# 380_PCB_Design.net
KiCad netlist of a schematic drawn in Altium Designer
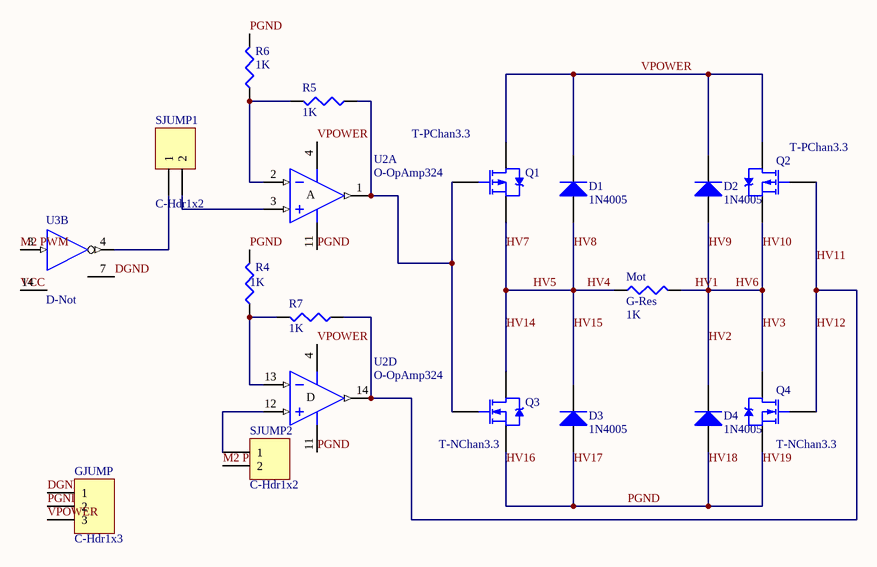
[diagram p0: 380 PCB Design.SchDoc]

(export (version "E")
  (design (tool "Eeschema 10.0.6"))
  (components
    (comp (ref "D1")
      (value "1N4005")
      (footprint "DO-41_XLGE1.2")
      (description "diode")
      (fields (field (name "PUBLISHER") "Altium Limited"))
      (libsource (lib "PartsDatabaseV12") (part "T-Diode-1N4005"))
    )
    (comp (ref "D2")
      (value "1N4005")
      (footprint "DO-41_XLGE1.2")
      (description "diode")
      (fields (field (name "PUBLISHER") "Altium Limited"))
      (libsource (lib "PartsDatabaseV12") (part "T-Diode-1N4005"))
    )
    (comp (ref "D3")
      (value "1N4005")
      (footprint "DO-41_XLGE1.2")
      (description "diode")
      (fields (field (name "PUBLISHER") "Altium Limited"))
      (libsource (lib "PartsDatabaseV12") (part "T-Diode-1N4005"))
    )
    (comp (ref "D4")
      (value "1N4005")
      (footprint "DO-41_XLGE1.2")
      (description "diode")
      (fields (field (name "PUBLISHER") "Altium Limited"))
      (libsource (lib "PartsDatabaseV12") (part "T-Diode-1N4005"))
    )
    (comp (ref "GJUMP")
      (value "C-Hdr1x3")
      (footprint "HDR1X3_LGE1.0")
      (description "Header, 4-Pin")
      (fields (field (name "PUBLISHER") "Altium Limited"))
      (libsource (lib "PartsDatabaseV13p1") (part "C-Hdr1x3"))
    )
    (comp (ref "Mot")
      (value "G-Res")
      (footprint "Res10mm_LGE1.0")
      (description "resistor (specify value)")
      (fields (field (name "ALTIUM_VALUE") "1K") (field (name "PUBLISHER") "Altium Limited"))
      (libsource (lib "PartsDatabaseV13p1") (part "G-Res"))
    )
    (comp (ref "Q1")
      (value "T-PChan3.3")
      (footprint "TO-220AB")
      (description "P-Channel Power MOSFET")
      (libsource (lib "PartsDatabaseV13p1") (part "T-PChan3.3"))
    )
    (comp (ref "Q2")
      (value "T-PChan3.3")
      (footprint "TO-220AB")
      (description "P-Channel Power MOSFET")
      (libsource (lib "PartsDatabaseV13p1") (part "T-PChan3.3"))
    )
    (comp (ref "Q3")
      (value "T-NChan3.3")
      (footprint "TO-220AB")
      (description "N-Channel Power MOSFET")
      (libsource (lib "PartsDatabaseV13p1") (part "T-NChan3.3"))
    )
    (comp (ref "Q4")
      (value "T-NChan3.3")
      (footprint "TO-220AB")
      (description "N-Channel Power MOSFET")
      (libsource (lib "PartsDatabaseV13p1") (part "T-NChan3.3"))
    )
    (comp (ref "R4")
      (value "1K")
      (footprint "Res10mm_LGE1.0")
      (description "resistor (specify value)")
      (fields (field (name "PUBLISHER") "Altium Limited"))
      (libsource (lib "PartsDatabaseV13p1") (part "G-Res"))
    )
    (comp (ref "R5")
      (value "1K")
      (footprint "Res10mm_LGE1.0")
      (description "resistor (specify value)")
      (fields (field (name "PUBLISHER") "Altium Limited"))
      (libsource (lib "PartsDatabaseV13p1") (part "G-Res"))
    )
    (comp (ref "R6")
      (value "1K")
      (footprint "Res10mm_LGE1.0")
      (description "resistor (specify value)")
      (fields (field (name "PUBLISHER") "Altium Limited"))
      (libsource (lib "PartsDatabaseV13p1") (part "G-Res"))
    )
    (comp (ref "R7")
      (value "1K")
      (footprint "Res10mm_LGE1.0")
      (description "resistor (specify value)")
      (fields (field (name "PUBLISHER") "Altium Limited"))
      (libsource (lib "PartsDatabaseV13p1") (part "G-Res"))
    )
    (comp (ref "SJUMP1")
      (value "C-Hdr1x2")
      (footprint "HDR1X2_LGE1.0")
      (description "Header, 2-Pin")
      (fields (field (name "PUBLISHER") "Altium Limited"))
      (libsource (lib "PartsDatabaseV13p1") (part "C-Hdr1x2"))
    )
    (comp (ref "SJUMP2")
      (value "C-Hdr1x2")
      (footprint "HDR1X2_LGE1.0")
      (description "Header, 2-Pin")
      (fields (field (name "PUBLISHER") "Altium Limited"))
      (libsource (lib "") (part "C-Hdr1x2_1"))
    )
    (comp (ref "U2")
      (value "O-OpAmp324")
      (footprint "DIP14_LGE1.0")
      (description "quad op-amp")
      (fields (field (name "PUBLISHER") "Altium Limited"))
      (libsource (lib "PartsDatabaseV13p1") (part "O-OpAmp324"))
    )
    (comp (ref "U3")
      (value "D-Not")
      (footprint "DIP14_LGE1.0")
      (description "hex NOT gate (inverter)")
      (fields (field (name "PUBLISHER") "Altium Limited"))
      (libsource (lib "PartsDatabaseV13p1") (part "D-Not"))
    )
  )
  (nets
    (net (code "1") (name "/DGND") (class "Default")
      (node (ref "GJUMP") (pin "1") (pinfunction "1_1") (pintype "passive"))
      (node (ref "U3") (pin "7") (pinfunction "GND_7") (pintype "power_in"))
    )
    (net (code "2") (name "/HV1") (class "Default")
      (node (ref "D2") (pin "1") (pinfunction "A_1") (pintype "passive"))
      (node (ref "D4") (pin "2") (pinfunction "K_2") (pintype "passive"))
      (node (ref "Mot") (pin "2") (pinfunction "2_2") (pintype "passive"))
      (node (ref "Q2") (pin "3") (pinfunction "S_3") (pintype "passive"))
      (node (ref "Q4") (pin "2") (pinfunction "D_2") (pintype "passive"))
    )
    (net (code "3") (name "/HV11") (class "Default")
      (node (ref "Q2") (pin "1") (pinfunction "G_1") (pintype "passive"))
      (node (ref "Q4") (pin "1") (pinfunction "G_1") (pintype "passive"))
      (node (ref "R7") (pin "1") (pinfunction "1_1") (pintype "passive"))
      (node (ref "U2") (pin "14") (pinfunction "OUT_14") (pintype "output"))
    )
    (net (code "4") (name "/HV14") (class "Default")
      (node (ref "D1") (pin "1") (pinfunction "A_1") (pintype "passive"))
      (node (ref "D3") (pin "2") (pinfunction "K_2") (pintype "passive"))
      (node (ref "Mot") (pin "1") (pinfunction "1_1") (pintype "passive"))
      (node (ref "Q1") (pin "3") (pinfunction "S_3") (pintype "passive"))
      (node (ref "Q3") (pin "2") (pinfunction "D_2") (pintype "passive"))
    )
    (net (code "5") (name "/HV16") (class "Default")
      (node (ref "D3") (pin "1") (pinfunction "A_1") (pintype "passive"))
      (node (ref "D4") (pin "1") (pinfunction "A_1") (pintype "passive"))
      (node (ref "GJUMP") (pin "2") (pinfunction "2_2") (pintype "passive"))
      (node (ref "Q3") (pin "3") (pinfunction "S_3") (pintype "passive"))
      (node (ref "Q4") (pin "3") (pinfunction "S_3") (pintype "passive"))
      (node (ref "R4") (pin "2") (pinfunction "2_2") (pintype "passive"))
      (node (ref "R6") (pin "2") (pinfunction "2_2") (pintype "passive"))
      (node (ref "U2") (pin "11") (pinfunction "V-_11") (pintype "power_in"))
    )
    (net (code "6") (name "/M2 PWM") (class "Default")
      (node (ref "SJUMP2") (pin "2") (pinfunction "2_2") (pintype "passive"))
      (node (ref "U3") (pin "3") (pinfunction "A_3") (pintype "input"))
    )
    (net (code "7") (name "/VCC") (class "Default")
      (node (ref "U3") (pin "14") (pinfunction "VCC_14") (pintype "power_in"))
    )
    (net (code "8") (name "/VPOWER") (class "Default")
      (node (ref "D1") (pin "2") (pinfunction "K_2") (pintype "passive"))
      (node (ref "D2") (pin "2") (pinfunction "K_2") (pintype "passive"))
      (node (ref "GJUMP") (pin "3") (pinfunction "3_3") (pintype "passive"))
      (node (ref "Q1") (pin "2") (pinfunction "D_2") (pintype "passive"))
      (node (ref "Q2") (pin "2") (pinfunction "D_2") (pintype "passive"))
      (node (ref "U2") (pin "4") (pinfunction "V+_4") (pintype "power_in"))
    )
    (net (code "9") (name "Net-(Q1-G)") (class "Default")
      (node (ref "Q1") (pin "1") (pinfunction "G_1") (pintype "passive"))
      (node (ref "Q3") (pin "1") (pinfunction "G_1") (pintype "passive"))
      (node (ref "R5") (pin "1") (pinfunction "1_1") (pintype "passive"))
      (node (ref "U2") (pin "1") (pinfunction "OUT_1") (pintype "output"))
    )
    (net (code "10") (name "Net-(U2A-IN+)") (class "Default")
      (node (ref "SJUMP1") (pin "2") (pinfunction "2_2") (pintype "passive"))
      (node (ref "U2") (pin "3") (pinfunction "IN+_3") (pintype "input"))
    )
    (net (code "11") (name "Net-(U2A-IN-)") (class "Default")
      (node (ref "R5") (pin "2") (pinfunction "2_2") (pintype "passive"))
      (node (ref "R6") (pin "1") (pinfunction "1_1") (pintype "passive"))
      (node (ref "U2") (pin "2") (pinfunction "IN-_2") (pintype "input"))
    )
    (net (code "12") (name "Net-(U2D-IN+)") (class "Default")
      (node (ref "SJUMP2") (pin "1") (pinfunction "1_1") (pintype "passive"))
      (node (ref "U2") (pin "12") (pinfunction "IN+_12") (pintype "input"))
    )
    (net (code "13") (name "Net-(U2D-IN-)") (class "Default")
      (node (ref "R4") (pin "1") (pinfunction "1_1") (pintype "passive"))
      (node (ref "R7") (pin "2") (pinfunction "2_2") (pintype "passive"))
      (node (ref "U2") (pin "13") (pinfunction "IN-_13") (pintype "input"))
    )
    (net (code "14") (name "Net-(U3B-Y)") (class "Default")
      (node (ref "SJUMP1") (pin "1") (pinfunction "1_1") (pintype "passive"))
      (node (ref "U3") (pin "4") (pinfunction "Y_4") (pintype "output"))
    )
  )
)
